# Quad_v1_0.net
KiCad netlist of a schematic drawn in EAGLE
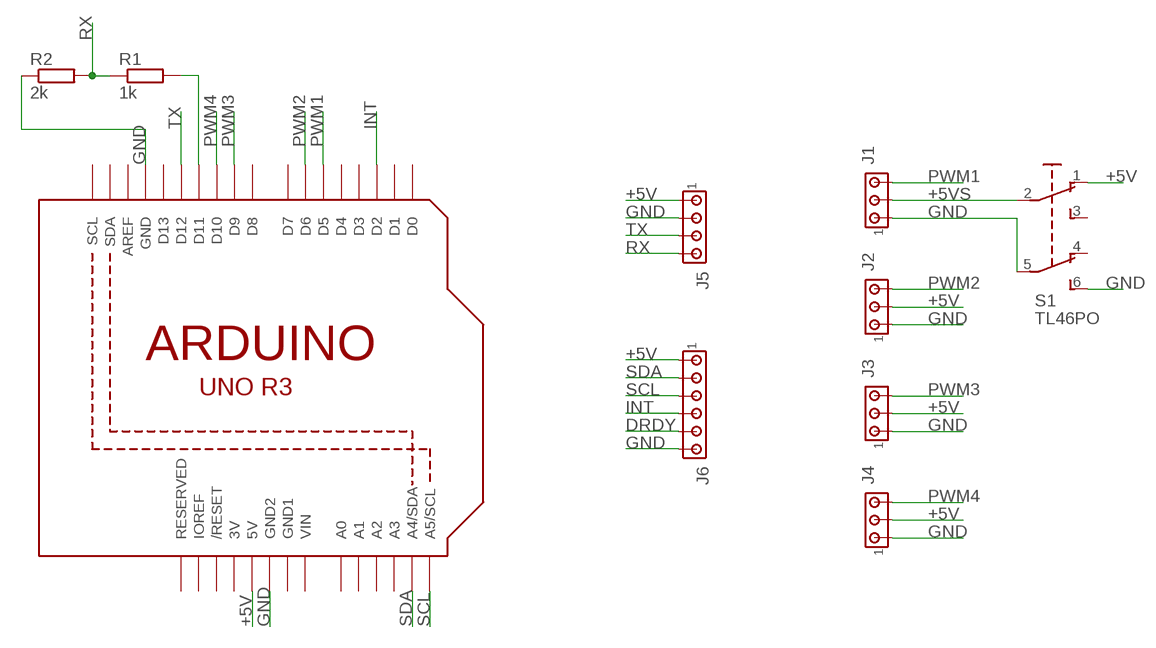
[diagram p0: schematic, sheet 1]

(export (version "E")
  (design (tool "Eeschema 10.0.6"))
  (components
    (comp (ref "J1")
      (value "MTA03-100")
      (footprint "eagle-import:10X03MTA")
      (libsource (lib "eagle-import") (part "MTA03-100"))
    )
    (comp (ref "J2")
      (value "MTA03-100")
      (footprint "eagle-import:10X03MTA")
      (libsource (lib "eagle-import") (part "MTA03-100"))
    )
    (comp (ref "J3")
      (value "MTA03-100")
      (footprint "eagle-import:10X03MTA")
      (libsource (lib "eagle-import") (part "MTA03-100"))
    )
    (comp (ref "J4")
      (value "MTA03-100")
      (footprint "eagle-import:10X03MTA")
      (libsource (lib "eagle-import") (part "MTA03-100"))
    )
    (comp (ref "J5")
      (value "MTA04-100")
      (footprint "eagle-import:10X04MTA")
      (libsource (lib "eagle-import") (part "MTA04-100"))
    )
    (comp (ref "J6")
      (value "MTA06-100")
      (footprint "eagle-import:10X06MTA")
      (libsource (lib "eagle-import") (part "MTA06-100"))
    )
    (comp (ref "R1")
      (value "1k")
      (footprint "eagle-import:0204_7")
      (libsource (lib "eagle-import") (part "R-EU_0204/7"))
    )
    (comp (ref "R2")
      (value "2k")
      (footprint "eagle-import:0204_7")
      (libsource (lib "eagle-import") (part "R-EU_0204/7"))
    )
    (comp (ref "S1")
      (value "TL46PO")
      (footprint "eagle-import:TL4XPO")
      (libsource (lib "eagle-import") (part "TL46PO"))
    )
    (comp (ref "U1")
      (value "ARDUINOR3-DIMENSION")
      (footprint "eagle-import:ARDUINOR3")
      (libsource (lib "eagle-import") (part "ARDUINOR3-DIMENSION"))
    )
  )
  (nets
    (net (code "1") (name "/+5V") (class "Default")
      (node (ref "J2") (pin "2") (pinfunction "2_2") (pintype "passive"))
      (node (ref "J3") (pin "2") (pinfunction "2_2") (pintype "passive"))
      (node (ref "J4") (pin "2") (pinfunction "2_2") (pintype "passive"))
      (node (ref "J5") (pin "1") (pinfunction "1_1") (pintype "passive"))
      (node (ref "J6") (pin "6") (pinfunction "1_6") (pintype "passive"))
      (node (ref "S1") (pin "1") (pinfunction "O_1") (pintype "passive"))
      (node (ref "U1") (pin "5V") (pinfunction "5V_5V") (pintype "power_in"))
    )
    (net (code "2") (name "/+5VS") (class "Default")
      (node (ref "J1") (pin "2") (pinfunction "2_2") (pintype "passive"))
      (node (ref "S1") (pin "2") (pinfunction "P_2") (pintype "passive"))
    )
    (net (code "3") (name "/3V") (class "Default")
      (node (ref "U1") (pin "3V") (pinfunction "3V_3V") (pintype "power_in"))
    )
    (net (code "4") (name "/DRDY") (class "Default")
      (node (ref "J6") (pin "2") (pinfunction "5_2") (pintype "passive"))
    )
    (net (code "5") (name "/GND") (class "Default")
      (node (ref "J1") (pin "1") (pinfunction "1_1") (pintype "passive"))
      (node (ref "J2") (pin "1") (pinfunction "1_1") (pintype "passive"))
      (node (ref "J3") (pin "1") (pinfunction "1_1") (pintype "passive"))
      (node (ref "J4") (pin "1") (pinfunction "1_1") (pintype "passive"))
      (node (ref "J5") (pin "2") (pinfunction "2_2") (pintype "passive"))
      (node (ref "J6") (pin "1") (pinfunction "6_1") (pintype "passive"))
      (node (ref "R2") (pin "1") (pinfunction "1_1") (pintype "passive"))
      (node (ref "S1") (pin "5") (pinfunction "P1_5") (pintype "passive"))
      (node (ref "S1") (pin "6") (pinfunction "S1_6") (pintype "passive"))
      (node (ref "U1") (pin "GND") (pinfunction "GND_GND") (pintype "power_in"))
      (node (ref "U1") (pin "GND2") (pinfunction "GND2_GND2") (pintype "power_in"))
    )
    (net (code "6") (name "/GND1") (class "Default")
      (node (ref "U1") (pin "GND1") (pinfunction "GND1_GND1") (pintype "power_in"))
    )
    (net (code "7") (name "/INT") (class "Default")
      (node (ref "J6") (pin "3") (pinfunction "4_3") (pintype "passive"))
      (node (ref "U1") (pin "D2") (pinfunction "D2_D2") (pintype "bidirectional"))
    )
    (net (code "8") (name "/PWM1") (class "Default")
      (node (ref "J1") (pin "3") (pinfunction "3_3") (pintype "passive"))
      (node (ref "U1") (pin "D5") (pinfunction "D5_D5") (pintype "bidirectional"))
    )
    (net (code "9") (name "/PWM2") (class "Default")
      (node (ref "J2") (pin "3") (pinfunction "3_3") (pintype "passive"))
      (node (ref "U1") (pin "D6") (pinfunction "D6_D6") (pintype "bidirectional"))
    )
    (net (code "10") (name "/PWM3") (class "Default")
      (node (ref "J3") (pin "3") (pinfunction "3_3") (pintype "passive"))
      (node (ref "U1") (pin "D9") (pinfunction "D9_D9") (pintype "bidirectional"))
    )
    (net (code "11") (name "/PWM4") (class "Default")
      (node (ref "J4") (pin "3") (pinfunction "3_3") (pintype "passive"))
      (node (ref "U1") (pin "D10") (pinfunction "D10_D10") (pintype "bidirectional"))
    )
    (net (code "12") (name "/RX") (class "Default")
      (node (ref "J5") (pin "4") (pinfunction "4_4") (pintype "passive"))
      (node (ref "R1") (pin "1") (pinfunction "1_1") (pintype "passive"))
      (node (ref "R2") (pin "2") (pinfunction "2_2") (pintype "passive"))
    )
    (net (code "13") (name "/SCL") (class "Default")
      (node (ref "J6") (pin "4") (pinfunction "3_4") (pintype "passive"))
      (node (ref "U1") (pin "A5") (pinfunction "A5/SCL_A5") (pintype "bidirectional"))
    )
    (net (code "14") (name "/SDA") (class "Default")
      (node (ref "J6") (pin "5") (pinfunction "2_5") (pintype "passive"))
      (node (ref "U1") (pin "A4") (pinfunction "A4/SDA_A4") (pintype "bidirectional"))
    )
    (net (code "15") (name "/TX") (class "Default")
      (node (ref "J5") (pin "3") (pinfunction "3_3") (pintype "passive"))
      (node (ref "U1") (pin "D12") (pinfunction "D12_D12") (pintype "bidirectional"))
    )
    (net (code "16") (name "/VIN") (class "Default")
      (node (ref "U1") (pin "VIN") (pinfunction "VIN_VIN") (pintype "power_in"))
    )
    (net (code "17") (name "Net-(R1-Pad2)") (class "Default")
      (node (ref "R1") (pin "2") (pinfunction "2_2") (pintype "passive"))
      (node (ref "U1") (pin "D11") (pinfunction "D11_D11") (pintype "bidirectional"))
    )
    (net (code "18") (name "unconnected-(S1-O1-Pad4)") (class "Default")
      (node (ref "S1") (pin "4") (pinfunction "O1_4") (pintype "passive"))
    )
    (net (code "19") (name "unconnected-(S1-S-Pad3)") (class "Default")
      (node (ref "S1") (pin "3") (pinfunction "S_3") (pintype "passive"))
    )
    (net (code "20") (name "unconnected-(U1-PadA0)") (class "Default")
      (node (ref "U1") (pin "A0") (pinfunction "A0_A0") (pintype "bidirectional"))
    )
    (net (code "21") (name "unconnected-(U1-PadA1)") (class "Default")
      (node (ref "U1") (pin "A1") (pinfunction "A1_A1") (pintype "bidirectional"))
    )
    (net (code "22") (name "unconnected-(U1-PadA2)") (class "Default")
      (node (ref "U1") (pin "A2") (pinfunction "A2_A2") (pintype "bidirectional"))
    )
    (net (code "23") (name "unconnected-(U1-PadA3)") (class "Default")
      (node (ref "U1") (pin "A3") (pinfunction "A3_A3") (pintype "bidirectional"))
    )
    (net (code "24") (name "unconnected-(U1-PadAREF)") (class "Default")
      (node (ref "U1") (pin "AREF") (pinfunction "AREF_AREF") (pintype "bidirectional"))
    )
    (net (code "25") (name "unconnected-(U1-PadD0)") (class "Default")
      (node (ref "U1") (pin "D0") (pinfunction "D0_D0") (pintype "bidirectional"))
    )
    (net (code "26") (name "unconnected-(U1-PadD1)") (class "Default")
      (node (ref "U1") (pin "D1") (pinfunction "D1_D1") (pintype "bidirectional"))
    )
    (net (code "27") (name "unconnected-(U1-PadD3)") (class "Default")
      (node (ref "U1") (pin "D3") (pinfunction "D3_D3") (pintype "bidirectional"))
    )
    (net (code "28") (name "unconnected-(U1-PadD4)") (class "Default")
      (node (ref "U1") (pin "D4") (pinfunction "D4_D4") (pintype "bidirectional"))
    )
    (net (code "29") (name "unconnected-(U1-PadD7)") (class "Default")
      (node (ref "U1") (pin "D7") (pinfunction "D7_D7") (pintype "bidirectional"))
    )
    (net (code "30") (name "unconnected-(U1-PadD8)") (class "Default")
      (node (ref "U1") (pin "D8") (pinfunction "D8_D8") (pintype "bidirectional"))
    )
    (net (code "31") (name "unconnected-(U1-PadD13)") (class "Default")
      (node (ref "U1") (pin "D13") (pinfunction "D13_D13") (pintype "bidirectional"))
    )
    (net (code "32") (name "unconnected-(U1-PadIOREF)") (class "Default")
      (node (ref "U1") (pin "IOREF") (pinfunction "IOREF_IOREF") (pintype "output"))
    )
    (net (code "33") (name "unconnected-(U1-PadRESERVED)") (class "Default")
      (node (ref "U1") (pin "RESERVED") (pinfunction "RESERVED_RESERVED") (pintype "no_connect"))
    )
    (net (code "34") (name "unconnected-(U1-PadSCL)") (class "Default")
      (node (ref "U1") (pin "SCL") (pinfunction "SCL_SCL") (pintype "bidirectional"))
    )
    (net (code "35") (name "unconnected-(U1-PadSDA)") (class "Default")
      (node (ref "U1") (pin "SDA") (pinfunction "SDA_SDA") (pintype "bidirectional"))
    )
    (net (code "36") (name "unconnected-(U1-{slash}RESET-PadRESET)") (class "Default")
      (node (ref "U1") (pin "RESET") (pinfunction "/RESET_RESET") (pintype "bidirectional"))
    )
  )
)
